# TSOC_PSoC4L.net
KiCad netlist of a schematic drawn in EAGLE
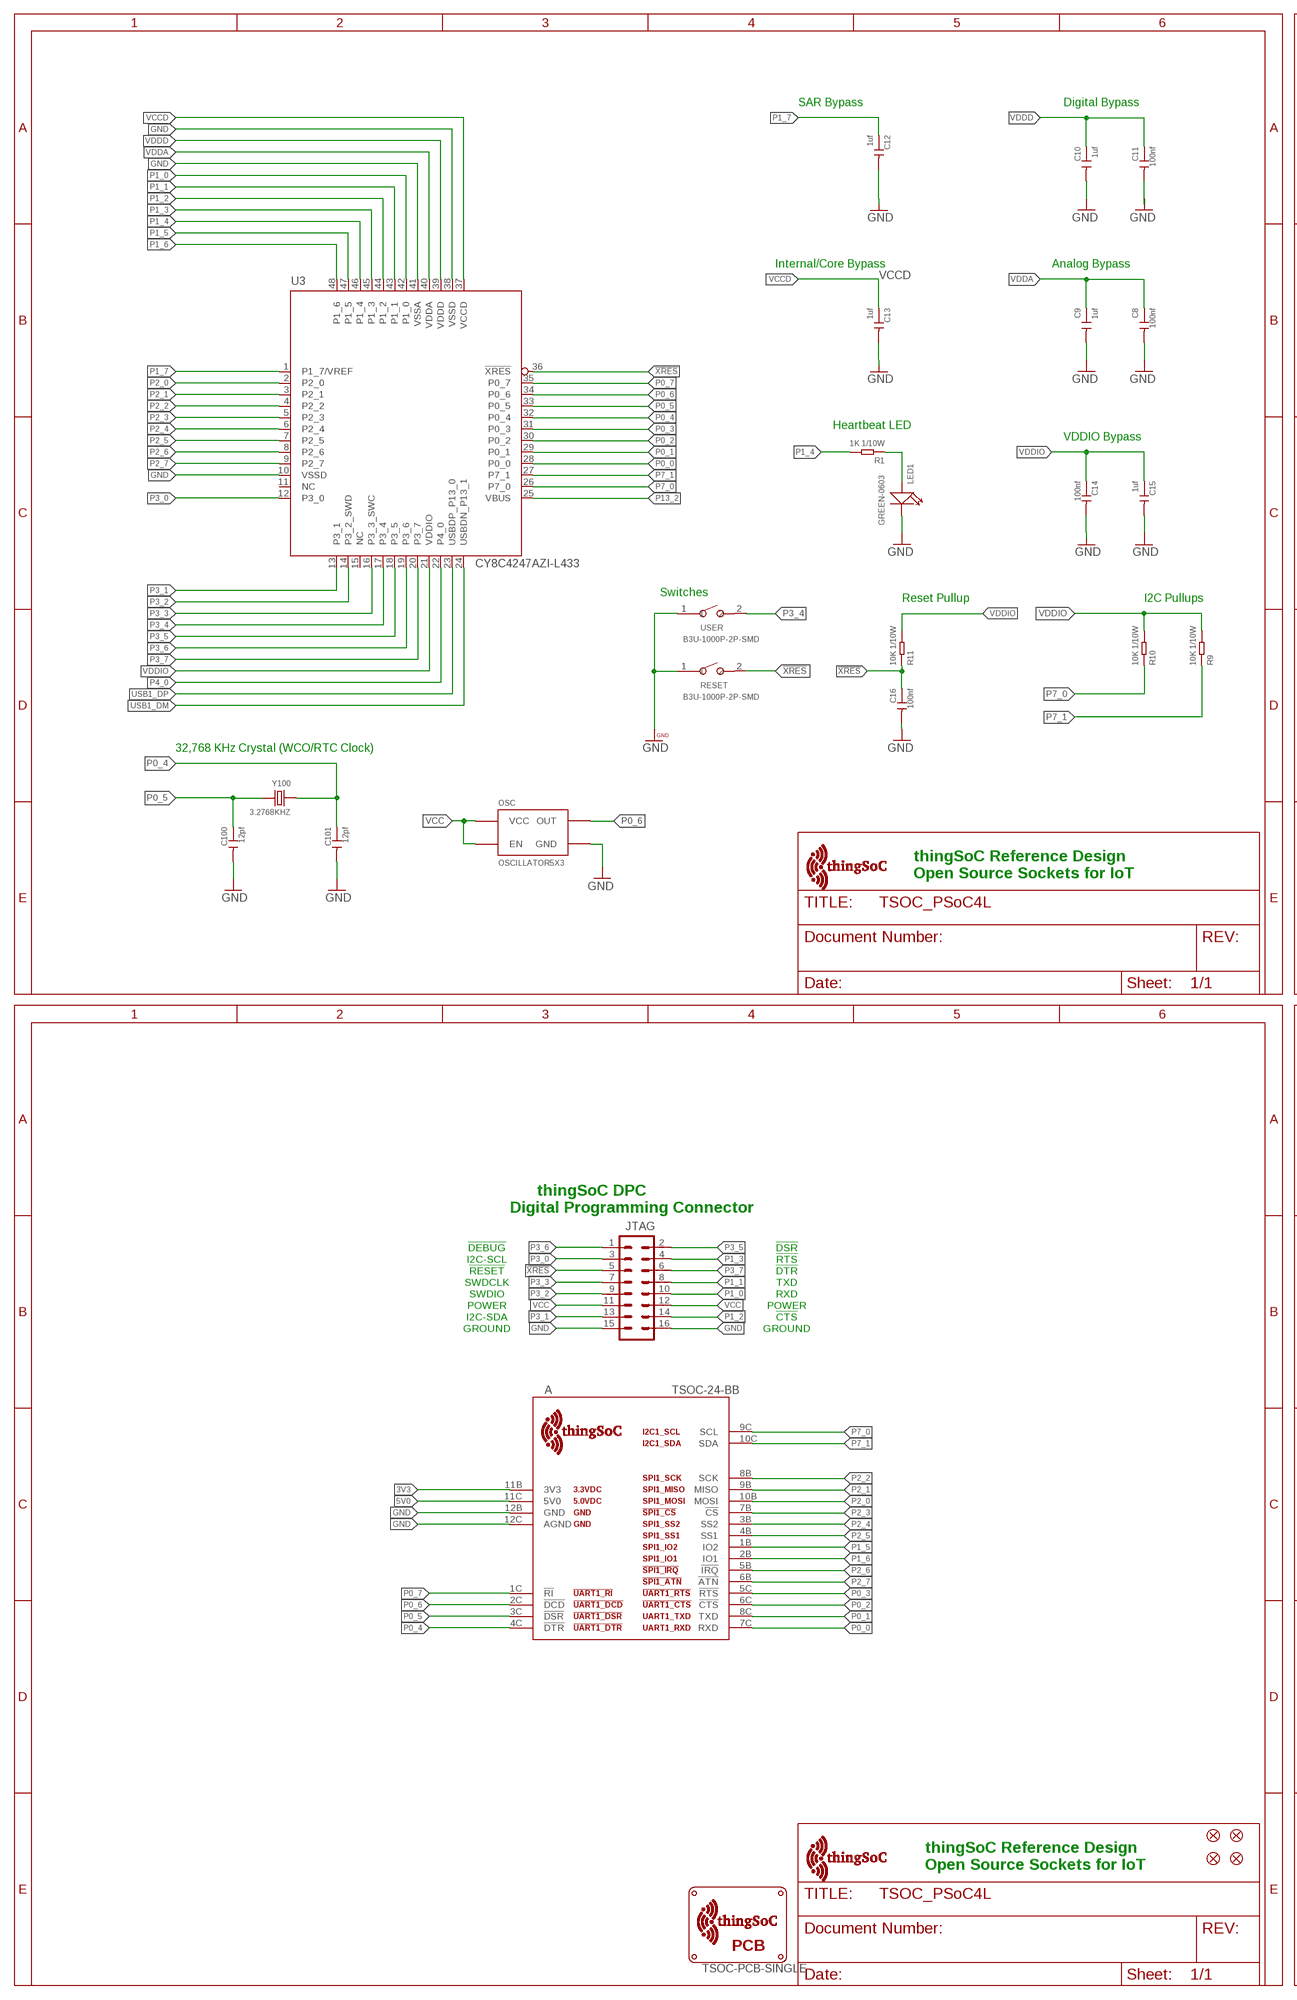
[diagram p0: schematic, sheet 1, part 1 of 2]
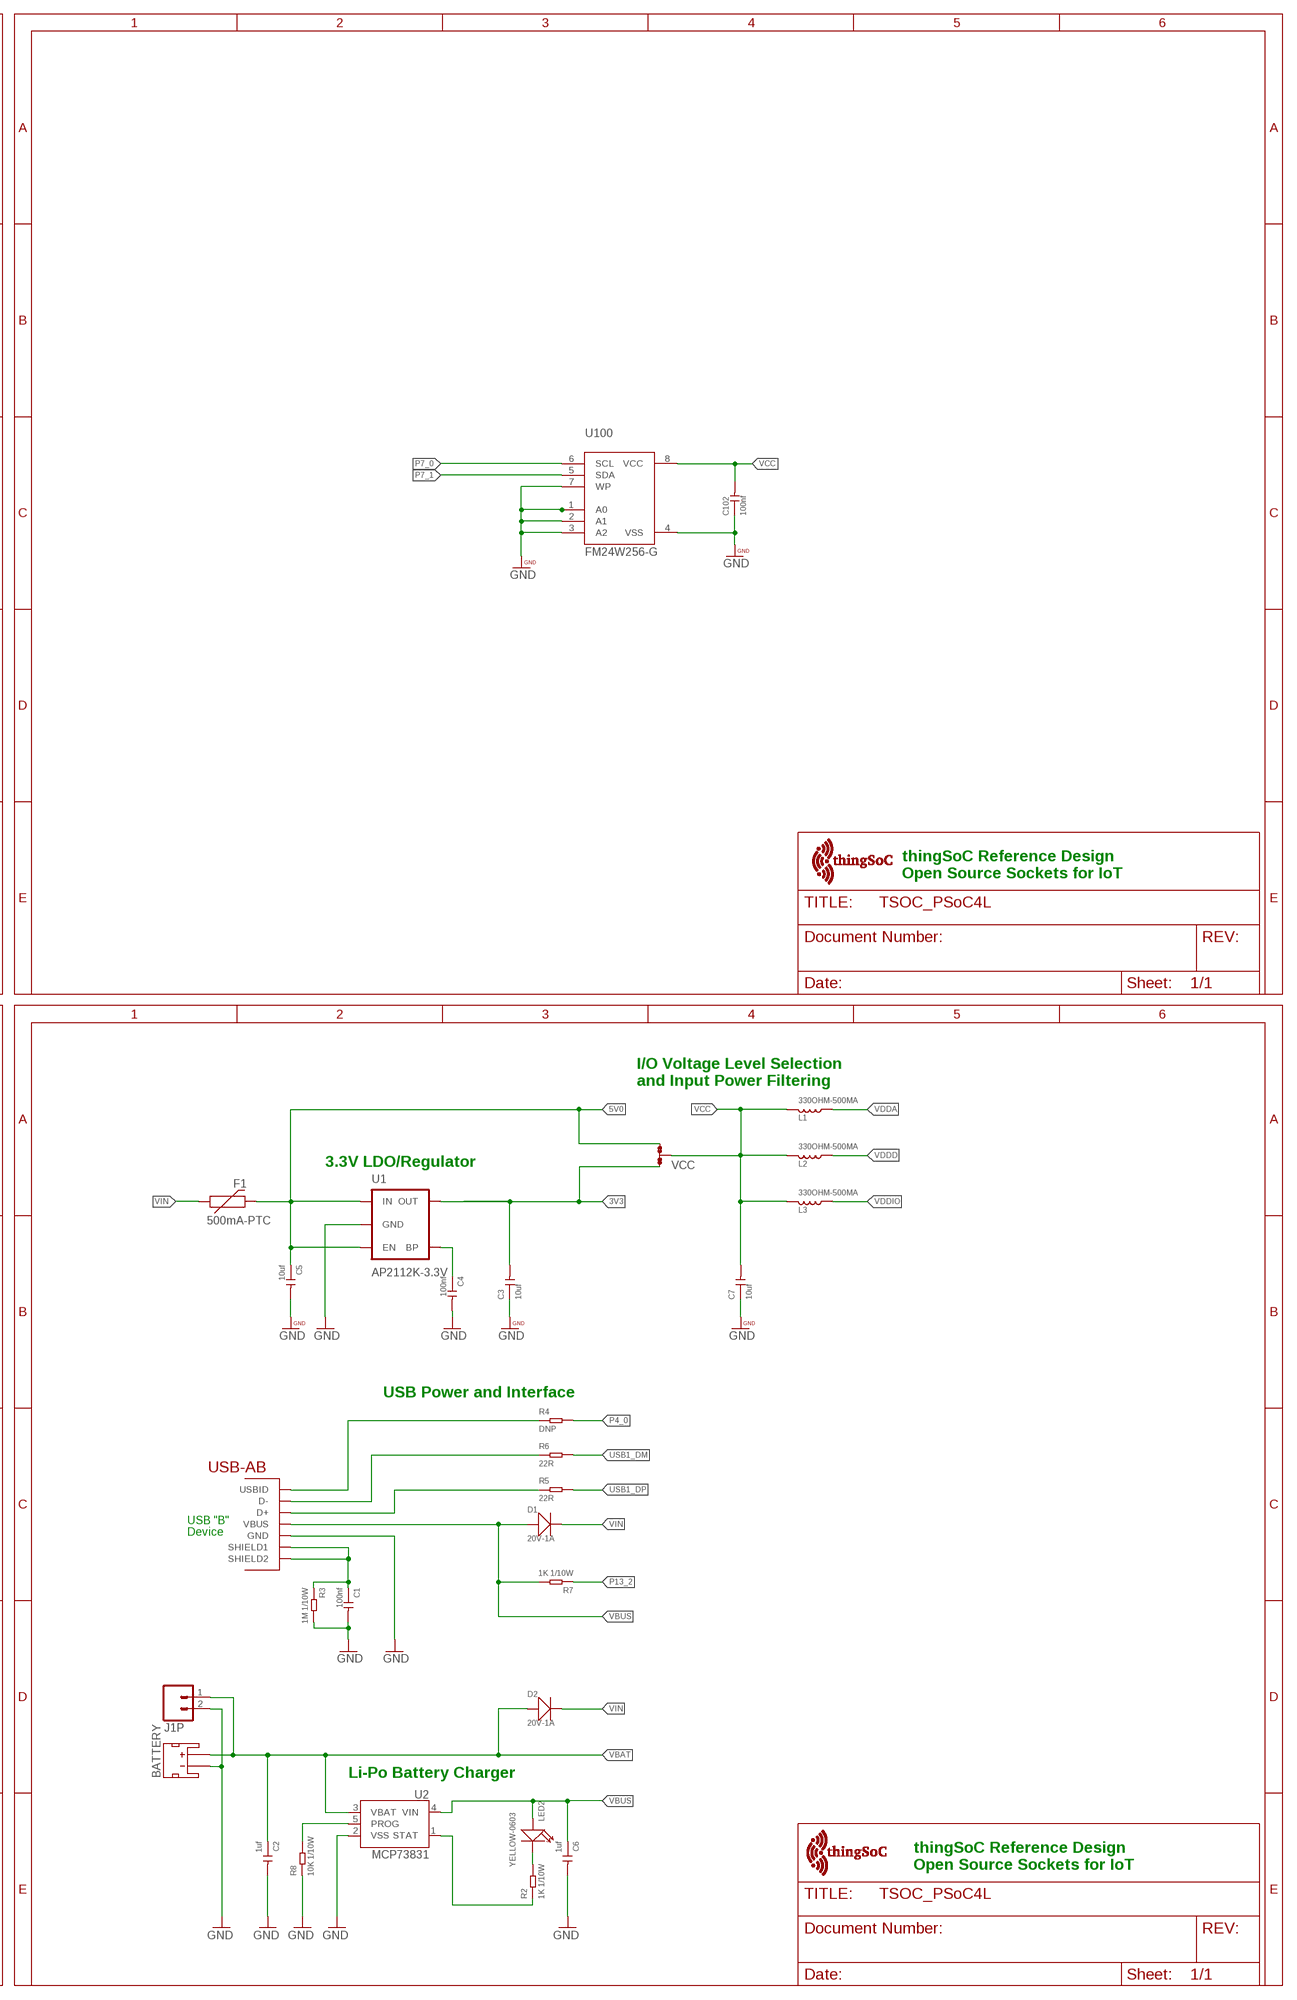
[diagram p1: schematic, sheet 1, part 2 of 2]

(export (version "E")
  (design (tool "Eeschema 10.0.6"))
  (components
    (comp (ref "$$U$1")
      (value "TSOC-LOGO-SMALL")
      (footprint "eagle-import:TSOC-LOGO-SML")
      (libsource (lib "eagle-import") (part "TSOC-LOGO-SMALL"))
    )
    (comp (ref "$$U$2")
      (value "TSOC-LOGO-SMALL")
      (footprint "eagle-import:TSOC-LOGO-SML")
      (libsource (lib "eagle-import") (part "TSOC-LOGO-SMALL"))
    )
    (comp (ref "A")
      (value "TSOC-24-BB")
      (footprint "eagle-import:TSOC-BB-S24")
      (libsource (lib "eagle-import") (part "TSOC-24-BB"))
    )
    (comp (ref "BATTERY")
      (value "JST_2MM_MALE")
      (footprint "eagle-import:JST-2-SMD")
      (libsource (lib "eagle-import") (part "JST_2MM_MALE"))
    )
    (comp (ref "C1")
      (value "100nf")
      (footprint "eagle-import:C0603")
      (fields (field (name "MPN") "CC0603KRX7R9BB104"))
      (libsource (lib "eagle-import") (part "CERAMIC-100NF-50V-10%-X7R(0603)"))
    )
    (comp (ref "C2")
      (value "1uf")
      (footprint "eagle-import:C0603")
      (fields (field (name "MPN") "CC0603KRX7R8BB105"))
      (libsource (lib "eagle-import") (part "CERAMIC-1UF-25V-10%-X7R(0603)"))
    )
    (comp (ref "C3")
      (value "10uf")
      (footprint "eagle-import:C0603")
      (fields (field (name "MPN") "CC0603KRX5R6BB106"))
      (libsource (lib "eagle-import") (part "CERAMIC-10UF-10V-10%-X5R(0603)"))
    )
    (comp (ref "C4")
      (value "100nf")
      (footprint "eagle-import:C0603")
      (fields (field (name "MPN") "CC0603KRX7R9BB104"))
      (libsource (lib "eagle-import") (part "CERAMIC-100NF-50V-10%-X7R(0603)"))
    )
    (comp (ref "C5")
      (value "10uf")
      (footprint "eagle-import:C0603")
      (fields (field (name "MPN") "CC0603KRX5R6BB106"))
      (libsource (lib "eagle-import") (part "CERAMIC-10UF-10V-10%-X5R(0603)"))
    )
    (comp (ref "C6")
      (value "1uf")
      (footprint "eagle-import:C0603")
      (fields (field (name "MPN") "CC0603KRX7R8BB105"))
      (libsource (lib "eagle-import") (part "CERAMIC-1UF-25V-10%-X7R(0603)"))
    )
    (comp (ref "C7")
      (value "10uf")
      (footprint "eagle-import:C0603")
      (fields (field (name "MPN") "CC0603KRX5R6BB106"))
      (libsource (lib "eagle-import") (part "CERAMIC-10UF-10V-10%-X5R(0603)"))
    )
    (comp (ref "C8")
      (value "100nf")
      (footprint "eagle-import:C0603")
      (fields (field (name "MPN") "CC0603KRX7R9BB104"))
      (libsource (lib "eagle-import") (part "CERAMIC-100NF-50V-10%-X7R(0603)"))
    )
    (comp (ref "C9")
      (value "1uf")
      (footprint "eagle-import:C0603")
      (fields (field (name "MPN") "CC0603KRX7R8BB105"))
      (libsource (lib "eagle-import") (part "CERAMIC-1UF-25V-10%-X7R(0603)"))
    )
    (comp (ref "C10")
      (value "1uf")
      (footprint "eagle-import:C0603")
      (fields (field (name "MPN") "CC0603KRX7R8BB105"))
      (libsource (lib "eagle-import") (part "CERAMIC-1UF-25V-10%-X7R(0603)"))
    )
    (comp (ref "C11")
      (value "100nf")
      (footprint "eagle-import:C0603")
      (fields (field (name "MPN") "CC0603KRX7R9BB104"))
      (libsource (lib "eagle-import") (part "CERAMIC-100NF-50V-10%-X7R(0603)"))
    )
    (comp (ref "C12")
      (value "1uf")
      (footprint "eagle-import:C0603")
      (fields (field (name "MPN") "CC0603KRX7R8BB105"))
      (libsource (lib "eagle-import") (part "CERAMIC-1UF-25V-10%-X7R(0603)"))
    )
    (comp (ref "C13")
      (value "1uf")
      (footprint "eagle-import:C0603")
      (fields (field (name "MPN") "CC0603KRX7R8BB105"))
      (libsource (lib "eagle-import") (part "CERAMIC-1UF-25V-10%-X7R(0603)"))
    )
    (comp (ref "C14")
      (value "100nf")
      (footprint "eagle-import:C0603")
      (fields (field (name "MPN") "CC0603KRX7R9BB104"))
      (libsource (lib "eagle-import") (part "CERAMIC-100NF-50V-10%-X7R(0603)"))
    )
    (comp (ref "C15")
      (value "1uf")
      (footprint "eagle-import:C0603")
      (fields (field (name "MPN") "CC0603KRX7R8BB105"))
      (libsource (lib "eagle-import") (part "CERAMIC-1UF-25V-10%-X7R(0603)"))
    )
    (comp (ref "C16")
      (value "100nf")
      (footprint "eagle-import:C0603")
      (fields (field (name "MPN") "CC0603KRX7R9BB104"))
      (libsource (lib "eagle-import") (part "CERAMIC-100NF-50V-10%-X7R(0603)"))
    )
    (comp (ref "C100")
      (value "12pf")
      (footprint "eagle-import:C0603")
      (fields (field (name "MPN") "CC0603JRNPO9BN120"))
      (libsource (lib "eagle-import") (part "CERAMIC-12PF-50V-5%-NPO(0603)"))
    )
    (comp (ref "C101")
      (value "12pf")
      (footprint "eagle-import:C0603")
      (fields (field (name "MPN") "CC0603JRNPO9BN120"))
      (libsource (lib "eagle-import") (part "CERAMIC-12PF-50V-5%-NPO(0603)"))
    )
    (comp (ref "C102")
      (value "100nf")
      (footprint "eagle-import:C0603")
      (fields (field (name "MPN") "CC0603KRX7R9BB104"))
      (libsource (lib "eagle-import") (part "CERAMIC-100NF-50V-10%-X7R(0603)"))
    )
    (comp (ref "D1")
      (value "20V-1A")
      (footprint "eagle-import:SOD-123")
      (fields (field (name "MPN") "B5819W"))
      (libsource (lib "eagle-import") (part "SMD-DIODE-SCHOTTKY-20V-1A(SOD-123)"))
    )
    (comp (ref "D2")
      (value "20V-1A")
      (footprint "eagle-import:SOD-123")
      (fields (field (name "MPN") "B5819W"))
      (libsource (lib "eagle-import") (part "SMD-DIODE-SCHOTTKY-20V-1A(SOD-123)"))
    )
    (comp (ref "F1")
      (value "500mA-PTC")
      (footprint "eagle-import:PTC-1206")
      (libsource (lib "eagle-import") (part "PTCSMD"))
    )
    (comp (ref "FID1")
      (value "FIDUCIALUFIDUCIAL")
      (footprint "eagle-import:MICRO-FIDUCIAL")
      (libsource (lib "eagle-import") (part "FIDUCIALUFIDUCIAL"))
    )
    (comp (ref "FID2")
      (value "FIDUCIALUFIDUCIAL")
      (footprint "eagle-import:MICRO-FIDUCIAL")
      (libsource (lib "eagle-import") (part "FIDUCIALUFIDUCIAL"))
    )
    (comp (ref "FID3")
      (value "FIDUCIALUFIDUCIAL")
      (footprint "eagle-import:MICRO-FIDUCIAL")
      (libsource (lib "eagle-import") (part "FIDUCIALUFIDUCIAL"))
    )
    (comp (ref "FID4")
      (value "FIDUCIALUFIDUCIAL")
      (footprint "eagle-import:MICRO-FIDUCIAL")
      (libsource (lib "eagle-import") (part "FIDUCIALUFIDUCIAL"))
    )
    (comp (ref "J1P")
      (value "M02-JST-2-PTH-NO_SILK")
      (footprint "eagle-import:JST-2-PTH-NS")
      (libsource (lib "eagle-import") (part "M02-JST-2-PTH-NO_SILK"))
    )
    (comp (ref "JTAG")
      (value "M08X2")
      (footprint "eagle-import:2X8")
      (libsource (lib "eagle-import") (part "M08X2"))
    )
    (comp (ref "L1")
      (value "330OHM-500MA")
      (footprint "eagle-import:L0603")
      (fields (field (name "MPN") "BLM18AG121SN1D"))
      (libsource (lib "eagle-import") (part "SMD-FERRITE-CHIP-120-OHM-500MA(0603)"))
    )
    (comp (ref "L2")
      (value "330OHM-500MA")
      (footprint "eagle-import:L0603")
      (fields (field (name "MPN") "BLM18AG121SN1D"))
      (libsource (lib "eagle-import") (part "SMD-FERRITE-CHIP-120-OHM-500MA(0603)"))
    )
    (comp (ref "L3")
      (value "330OHM-500MA")
      (footprint "eagle-import:L0603")
      (fields (field (name "MPN") "BLM18AG121SN1D"))
      (libsource (lib "eagle-import") (part "SMD-FERRITE-CHIP-120-OHM-500MA(0603)"))
    )
    (comp (ref "LED1")
      (value "GREEN-0603")
      (footprint "eagle-import:LED-0603")
      (fields (field (name "MPN") "19-217-G7C-AN1P2-3T"))
      (libsource (lib "eagle-import") (part "SMD-LED-CLEAR-GREEN(0603)"))
    )
    (comp (ref "LED2")
      (value "YELLOW-0603")
      (footprint "eagle-import:LED-0603")
      (fields (field (name "MPN") "19-217-Y5C-AM1N1VY-3T"))
      (libsource (lib "eagle-import") (part "SMD-LED-CLEAR-YELLOW(0603)"))
    )
    (comp (ref "OSC")
      (value "OSCILLATOR5X3")
      (footprint "eagle-import:CRYSTAL-SMD-5X3")
      (libsource (lib "eagle-import") (part "OSCILLATOR5X3"))
    )
    (comp (ref "R1")
      (value "1K 1/10W")
      (footprint "eagle-import:R0603")
      (fields (field (name "MPN") "RC0603JR-071KL"))
      (libsource (lib "eagle-import") (part "SMD-RES-1K-5%-1/10W(0603)"))
    )
    (comp (ref "R2")
      (value "1K 1/10W")
      (footprint "eagle-import:R0603")
      (fields (field (name "MPN") "RC0603JR-071KL"))
      (libsource (lib "eagle-import") (part "SMD-RES-1K-5%-1/10W(0603)"))
    )
    (comp (ref "R3")
      (value "1M 1/10W")
      (footprint "eagle-import:R0603")
      (fields (field (name "MPN") "RC0603JR-071ML"))
      (libsource (lib "eagle-import") (part "SMD-RES-1M-5%-1/10W(0603)"))
    )
    (comp (ref "R4")
      (value "DNP")
      (footprint "eagle-import:R0603")
      (fields (field (name "MPN") "RC0603JR-0722RL"))
      (libsource (lib "eagle-import") (part "SMD-RES-22R-5%-1/10W(0603)"))
    )
    (comp (ref "R5")
      (value "22R")
      (footprint "eagle-import:R0603")
      (fields (field (name "MPN") "RC0603JR-0722RL"))
      (libsource (lib "eagle-import") (part "SMD-RES-22R-5%-1/10W(0603)"))
    )
    (comp (ref "R6")
      (value "22R")
      (footprint "eagle-import:R0603")
      (fields (field (name "MPN") "RC0603JR-0722RL"))
      (libsource (lib "eagle-import") (part "SMD-RES-22R-5%-1/10W(0603)"))
    )
    (comp (ref "R7")
      (value "1K 1/10W")
      (footprint "eagle-import:R0603")
      (fields (field (name "MPN") "RC0603JR-071KL"))
      (libsource (lib "eagle-import") (part "SMD-RES-1K-5%-1/10W(0603)"))
    )
    (comp (ref "R8")
      (value "10K 1/10W")
      (footprint "eagle-import:R0603")
      (fields (field (name "MPN") "RC0603JR-0710KL"))
      (libsource (lib "eagle-import") (part "SMD-RES-10K-5%-1/10W(0603)"))
    )
    (comp (ref "R9")
      (value "10K 1/10W")
      (footprint "eagle-import:R0603")
      (fields (field (name "MPN") "RC0603JR-0710KL"))
      (libsource (lib "eagle-import") (part "SMD-RES-10K-5%-1/10W(0603)"))
    )
    (comp (ref "R10")
      (value "10K 1/10W")
      (footprint "eagle-import:R0603")
      (fields (field (name "MPN") "RC0603JR-0710KL"))
      (libsource (lib "eagle-import") (part "SMD-RES-10K-5%-1/10W(0603)"))
    )
    (comp (ref "R11")
      (value "10K 1/10W")
      (footprint "eagle-import:R0603")
      (fields (field (name "MPN") "RC0603JR-0710KL"))
      (libsource (lib "eagle-import") (part "SMD-RES-10K-5%-1/10W(0603)"))
    )
    (comp (ref "RESET")
      (value "B3U-1000P-2P-SMD")
      (footprint "eagle-import:SW2-2.6-3.0X2.5X1.2+0.4MM")
      (libsource (lib "eagle-import") (part "SMD-BUTTON(2P-3.0X2.5X1.2+0.4MM)-B3U-1000P-2P-SMD"))
    )
    (comp (ref "U$1")
      (value "TSOC-PCB-SINGLE")
      (footprint "eagle-import:TSOC-BB-BRD-DIM")
      (libsource (lib "eagle-import") (part "TSOC-PCB-SINGLE"))
    )
    (comp (ref "U$100")
      (value "TSOC-LOGO-LRG")
      (footprint "eagle-import:TSOC-LOGO-LRG")
      (libsource (lib "eagle-import") (part "TSOC-LOGO-LRG"))
    )
    (comp (ref "U$101")
      (value "TSOC-LOGO-SMALL")
      (footprint "eagle-import:TSOC-LOGO-SML")
      (libsource (lib "eagle-import") (part "TSOC-LOGO-SMALL"))
    )
    (comp (ref "U1")
      (value "AP2112K-3.3V")
      (footprint "eagle-import:SOT23-5")
      (libsource (lib "eagle-import") (part "V_REG_LDOSMD"))
    )
    (comp (ref "U2")
      (value "MCP73831")
      (footprint "eagle-import:SOT23-5")
      (libsource (lib "eagle-import") (part "MCP73831"))
    )
    (comp (ref "U3")
      (value "CY8C4247AZI-L433")
      (footprint "eagle-import:TQFP-7X7-48")
      (libsource (lib "eagle-import") (part "CY8C4247AZI-L433"))
    )
    (comp (ref "U100")
      (value "FM24W256-G")
      (footprint "eagle-import:SO08")
      (libsource (lib "eagle-import") (part "FM24W256-G"))
    )
    (comp (ref "USB")
      (value "USB_AB")
      (footprint "eagle-import:USB-AB-MICRO-SMD")
      (libsource (lib "eagle-import") (part "USB_AB"))
    )
    (comp (ref "USER")
      (value "B3U-1000P-2P-SMD")
      (footprint "eagle-import:SW2-2.6-3.0X2.5X1.2+0.4MM")
      (libsource (lib "eagle-import") (part "SMD-BUTTON(2P-3.0X2.5X1.2+0.4MM)-B3U-1000P-2P-SMD"))
    )
    (comp (ref "VCC")
      (value "JMP-3-1_2")
      (footprint "eagle-import:JMP-3-1_2")
      (libsource (lib "eagle-import") (part "JMP-3-1_2"))
    )
    (comp (ref "Y100")
      (value "3.2768KHZ")
      (footprint "eagle-import:X2-SMD-L2.0X1.2X0.55MM")
      (fields (field (name "MPN") "FC-12M"))
      (libsource (lib "eagle-import") (part "SMD-CRYSTAL-32.768KHZ-12.5PF-20PPM-90K(2P-L2.0X1.2MM)"))
    )
  )
  (nets
    (net (code "1") (name "/~{XRES}") (class "Default")
      (node (ref "C16") (pin "1") (pinfunction "1_1") (pintype "passive"))
      (node (ref "JTAG") (pin "5") (pinfunction "5_5") (pintype "passive"))
      (node (ref "R11") (pin "1") (pinfunction "1_1") (pintype "passive"))
      (node (ref "RESET") (pin "2") (pinfunction "2_2") (pintype "bidirectional"))
      (node (ref "U3") (pin "36") (pinfunction "~{XRES}_36") (pintype "bidirectional"))
    )
    (net (code "2") (name "3V3") (class "Default")
      (node (ref "A") (pin "11B") (pinfunction "3V3_11B") (pintype "bidirectional"))
      (node (ref "C3") (pin "2") (pinfunction "2_2") (pintype "passive"))
      (node (ref "U1") (pin "5") (pinfunction "OUT_5") (pintype "passive"))
      (node (ref "VCC") (pin "1") (pinfunction "1_1") (pintype "passive"))
    )
    (net (code "3") (name "5V0") (class "Default")
      (node (ref "A") (pin "11C") (pinfunction "5V0_11C") (pintype "bidirectional"))
      (node (ref "C5") (pin "1") (pinfunction "1_1") (pintype "passive"))
      (node (ref "F1") (pin "2") (pinfunction "2_2") (pintype "bidirectional"))
      (node (ref "U1") (pin "1") (pinfunction "IN_1") (pintype "input"))
      (node (ref "U1") (pin "3") (pinfunction "EN_3") (pintype "input"))
      (node (ref "VCC") (pin "3") (pinfunction "3_3") (pintype "passive"))
    )
    (net (code "4") (name "GND") (class "Default")
      (node (ref "A") (pin "12B") (pinfunction "GND_12B") (pintype "bidirectional"))
      (node (ref "A") (pin "12C") (pinfunction "AGND_12C") (pintype "bidirectional"))
      (node (ref "BATTERY") (pin "1") (pinfunction "-_1") (pintype "bidirectional"))
      (node (ref "C1") (pin "2") (pinfunction "2_2") (pintype "passive"))
      (node (ref "C10") (pin "2") (pinfunction "2_2") (pintype "passive"))
      (node (ref "C100") (pin "2") (pinfunction "2_2") (pintype "passive"))
      (node (ref "C101") (pin "2") (pinfunction "2_2") (pintype "passive"))
      (node (ref "C102") (pin "1") (pinfunction "1_1") (pintype "passive"))
      (node (ref "C11") (pin "2") (pinfunction "2_2") (pintype "passive"))
      (node (ref "C12") (pin "2") (pinfunction "2_2") (pintype "passive"))
      (node (ref "C13") (pin "2") (pinfunction "2_2") (pintype "passive"))
      (node (ref "C14") (pin "2") (pinfunction "2_2") (pintype "passive"))
      (node (ref "C15") (pin "2") (pinfunction "2_2") (pintype "passive"))
      (node (ref "C16") (pin "2") (pinfunction "2_2") (pintype "passive"))
      (node (ref "C2") (pin "2") (pinfunction "2_2") (pintype "passive"))
      (node (ref "C3") (pin "1") (pinfunction "1_1") (pintype "passive"))
      (node (ref "C4") (pin "2") (pinfunction "2_2") (pintype "passive"))
      (node (ref "C5") (pin "2") (pinfunction "2_2") (pintype "passive"))
      (node (ref "C6") (pin "2") (pinfunction "2_2") (pintype "passive"))
      (node (ref "C7") (pin "1") (pinfunction "1_1") (pintype "passive"))
      (node (ref "C8") (pin "2") (pinfunction "2_2") (pintype "passive"))
      (node (ref "C9") (pin "2") (pinfunction "2_2") (pintype "passive"))
      (node (ref "J1P") (pin "2") (pinfunction "2_2") (pintype "passive"))
      (node (ref "JTAG") (pin "15") (pinfunction "15_15") (pintype "passive"))
      (node (ref "JTAG") (pin "16") (pinfunction "16_16") (pintype "passive"))
      (node (ref "LED1") (pin "-") (pinfunction "-_-") (pintype "passive"))
      (node (ref "OSC") (pin "2") (pinfunction "GND_2") (pintype "bidirectional"))
      (node (ref "R3") (pin "2") (pinfunction "2_2") (pintype "passive"))
      (node (ref "R8") (pin "1") (pinfunction "1_1") (pintype "passive"))
      (node (ref "RESET") (pin "1") (pinfunction "1_1") (pintype "bidirectional"))
      (node (ref "U1") (pin "2") (pinfunction "GND_2") (pintype "input"))
      (node (ref "U100") (pin "1") (pinfunction "A0_1") (pintype "bidirectional"))
      (node (ref "U100") (pin "2") (pinfunction "A1_2") (pintype "bidirectional"))
      (node (ref "U100") (pin "3") (pinfunction "A2_3") (pintype "bidirectional"))
      (node (ref "U100") (pin "4") (pinfunction "VSS_4") (pintype "power_in"))
      (node (ref "U100") (pin "7") (pinfunction "WP_7") (pintype "bidirectional"))
      (node (ref "U2") (pin "2") (pinfunction "VSS_2") (pintype "power_in"))
      (node (ref "U3") (pin "10") (pinfunction "VSSD_10") (pintype "bidirectional"))
      (node (ref "U3") (pin "38") (pinfunction "VSSD_38") (pintype "bidirectional"))
      (node (ref "U3") (pin "41") (pinfunction "VSSA_41") (pintype "bidirectional"))
      (node (ref "USB") (pin "GND") (pinfunction "GND_GND") (pintype "bidirectional"))
      (node (ref "USER") (pin "1") (pinfunction "1_1") (pintype "bidirectional"))
    )
    (net (code "5") (name "Net-(C1-Pad1)") (class "Default")
      (node (ref "C1") (pin "1") (pinfunction "1_1") (pintype "passive"))
      (node (ref "R3") (pin "1") (pinfunction "1_1") (pintype "passive"))
      (node (ref "USB") (pin "SHIELD1") (pinfunction "SHIELD1_SHIELD1") (pintype "bidirectional"))
      (node (ref "USB") (pin "SHIELD2") (pinfunction "SHIELD2_SHIELD2") (pintype "bidirectional"))
    )
    (net (code "6") (name "Net-(LED1-Pad+)") (class "Default")
      (node (ref "LED1") (pin "+") (pinfunction "+_+") (pintype "passive"))
      (node (ref "R1") (pin "1") (pinfunction "1_1") (pintype "passive"))
    )
    (net (code "7") (name "Net-(LED2-Pad-)") (class "Default")
      (node (ref "LED2") (pin "-") (pinfunction "-_-") (pintype "passive"))
      (node (ref "R2") (pin "2") (pinfunction "2_2") (pintype "passive"))
    )
    (net (code "8") (name "Net-(R5-Pad1)") (class "Default")
      (node (ref "R5") (pin "1") (pinfunction "1_1") (pintype "passive"))
      (node (ref "USB") (pin "D+") (pinfunction "D+_D+") (pintype "bidirectional"))
    )
    (net (code "9") (name "Net-(R6-Pad1)") (class "Default")
      (node (ref "R6") (pin "1") (pinfunction "1_1") (pintype "passive"))
      (node (ref "USB") (pin "D-") (pinfunction "D-_D-") (pintype "bidirectional"))
    )
    (net (code "10") (name "Net-(U1-BP)") (class "Default")
      (node (ref "C4") (pin "1") (pinfunction "1_1") (pintype "passive"))
      (node (ref "U1") (pin "4") (pinfunction "BP_4") (pintype "input"))
    )
    (net (code "11") (name "Net-(U2-PROG)") (class "Default")
      (node (ref "R8") (pin "2") (pinfunction "2_2") (pintype "passive"))
      (node (ref "U2") (pin "5") (pinfunction "PROG_5") (pintype "input"))
    )
    (net (code "12") (name "Net-(U2-STAT)") (class "Default")
      (node (ref "R2") (pin "1") (pinfunction "1_1") (pintype "passive"))
      (node (ref "U2") (pin "1") (pinfunction "STAT_1") (pintype "output"))
    )
    (net (code "13") (name "Net-(USB-USBID)") (class "Default")
      (node (ref "R4") (pin "1") (pinfunction "1_1") (pintype "passive"))
      (node (ref "USB") (pin "ID") (pinfunction "USBID_ID") (pintype "bidirectional"))
    )
    (net (code "14") (name "P0_0") (class "Default")
      (node (ref "A") (pin "7C") (pinfunction "RXD_7C") (pintype "bidirectional"))
      (node (ref "U3") (pin "28") (pinfunction "P0_0_28") (pintype "bidirectional"))
    )
    (net (code "15") (name "P0_1") (class "Default")
      (node (ref "A") (pin "8C") (pinfunction "TXD_8C") (pintype "bidirectional"))
      (node (ref "U3") (pin "29") (pinfunction "P0_1_29") (pintype "bidirectional"))
    )
    (net (code "16") (name "P0_2") (class "Default")
      (node (ref "A") (pin "6C") (pinfunction "~{CTS}_6C") (pintype "bidirectional"))
      (node (ref "U3") (pin "30") (pinfunction "P0_2_30") (pintype "input"))
    )
    (net (code "17") (name "P0_3") (class "Default")
      (node (ref "A") (pin "5C") (pinfunction "~{RTS}_5C") (pintype "bidirectional"))
      (node (ref "U3") (pin "31") (pinfunction "P0_3_31") (pintype "bidirectional"))
    )
    (net (code "18") (name "P0_4") (class "Default")
      (node (ref "A") (pin "4C") (pinfunction "~{DTR}_4C") (pintype "bidirectional"))
      (node (ref "C101") (pin "1") (pinfunction "1_1") (pintype "passive"))
      (node (ref "U3") (pin "32") (pinfunction "P0_4_32") (pintype "bidirectional"))
      (node (ref "Y100") (pin "1") (pinfunction "1_1") (pintype "passive"))
    )
    (net (code "19") (name "P0_5") (class "Default")
      (node (ref "A") (pin "3C") (pinfunction "~{DSR}_3C") (pintype "bidirectional"))
      (node (ref "C100") (pin "1") (pinfunction "1_1") (pintype "passive"))
      (node (ref "U3") (pin "33") (pinfunction "P0_5_33") (pintype "bidirectional"))
      (node (ref "Y100") (pin "2") (pinfunction "2_2") (pintype "passive"))
    )
    (net (code "20") (name "P0_6") (class "Default")
      (node (ref "A") (pin "2C") (pinfunction "~{DCD}_2C") (pintype "bidirectional"))
      (node (ref "OSC") (pin "3") (pinfunction "OUT_3") (pintype "bidirectional"))
      (node (ref "U3") (pin "34") (pinfunction "P0_6_34") (pintype "power_in"))
    )
    (net (code "21") (name "P0_7") (class "Default")
      (node (ref "A") (pin "1C") (pinfunction "~{RI}_1C") (pintype "bidirectional"))
      (node (ref "U3") (pin "35") (pinfunction "P0_7_35") (pintype "bidirectional"))
    )
    (net (code "22") (name "P1_0") (class "Default")
      (node (ref "JTAG") (pin "10") (pinfunction "10_10") (pintype "passive"))
      (node (ref "U3") (pin "42") (pinfunction "P1_0_42") (pintype "bidirectional"))
    )
    (net (code "23") (name "P1_1") (class "Default")
      (node (ref "JTAG") (pin "8") (pinfunction "8_8") (pintype "passive"))
      (node (ref "U3") (pin "43") (pinfunction "P1_1_43") (pintype "bidirectional"))
    )
    (net (code "24") (name "P1_2") (class "Default")
      (node (ref "JTAG") (pin "14") (pinfunction "14_14") (pintype "passive"))
      (node (ref "U3") (pin "44") (pinfunction "P1_2_44") (pintype "power_in"))
    )
    (net (code "25") (name "P1_3") (class "Default")
      (node (ref "JTAG") (pin "4") (pinfunction "4_4") (pintype "passive"))
      (node (ref "U3") (pin "45") (pinfunction "P1_3_45") (pintype "bidirectional"))
    )
    (net (code "26") (name "P1_4") (class "Default")
      (node (ref "R1") (pin "2") (pinfunction "2_2") (pintype "passive"))
      (node (ref "U3") (pin "46") (pinfunction "P1_4_46") (pintype "bidirectional"))
    )
    (net (code "27") (name "P1_5") (class "Default")
      (node (ref "A") (pin "1B") (pinfunction "IO2_1B") (pintype "bidirectional"))
      (node (ref "U3") (pin "47") (pinfunction "P1_5_47") (pintype "bidirectional"))
    )
    (net (code "28") (name "P1_6") (class "Default")
      (node (ref "A") (pin "2B") (pinfunction "IO1_2B") (pintype "bidirectional"))
      (node (ref "U3") (pin "48") (pinfunction "P1_6_48") (pintype "bidirectional"))
    )
    (net (code "29") (name "P1_7") (class "Default")
      (node (ref "C12") (pin "1") (pinfunction "1_1") (pintype "passive"))
      (node (ref "U3") (pin "1") (pinfunction "P1_7/VREF_1") (pintype "bidirectional"))
    )
    (net (code "30") (name "P2_0") (class "Default")
      (node (ref "A") (pin "10B") (pinfunction "MOSI_10B") (pintype "bidirectional"))
      (node (ref "U3") (pin "2") (pinfunction "P2_0_2") (pintype "bidirectional"))
    )
    (net (code "31") (name "P2_1") (class "Default")
      (node (ref "A") (pin "9B") (pinfunction "MISO_9B") (pintype "bidirectional"))
      (node (ref "U3") (pin "3") (pinfunction "P2_1_3") (pintype "bidirectional"))
    )
    (net (code "32") (name "P2_2") (class "Default")
      (node (ref "A") (pin "8B") (pinfunction "SCK_8B") (pintype "bidirectional"))
      (node (ref "U3") (pin "4") (pinfunction "P2_2_4") (pintype "power_in"))
    )
    (net (code "33") (name "P2_3") (class "Default")
      (node (ref "A") (pin "7B") (pinfunction "~{CS}_7B") (pintype "bidirectional"))
      (node (ref "U3") (pin "5") (pinfunction "P2_3_5") (pintype "bidirectional"))
    )
    (net (code "34") (name "P2_4") (class "Default")
      (node (ref "A") (pin "3B") (pinfunction "SS2_3B") (pintype "bidirectional"))
      (node (ref "U3") (pin "6") (pinfunction "P2_4_6") (pintype "bidirectional"))
    )
    (net (code "35") (name "P2_5") (class "Default")
      (node (ref "A") (pin "4B") (pinfunction "SS1_4B") (pintype "bidirectional"))
      (node (ref "U3") (pin "7") (pinfunction "P2_5_7") (pintype "bidirectional"))
    )
    (net (code "36") (name "P2_6") (class "Default")
      (node (ref "A") (pin "5B") (pinfunction "~{IRQ}_5B") (pintype "bidirectional"))
      (node (ref "U3") (pin "8") (pinfunction "P2_6_8") (pintype "power_in"))
    )
    (net (code "37") (name "P2_7") (class "Default")
      (node (ref "A") (pin "6B") (pinfunction "~{ATN}_6B") (pintype "bidirectional"))
      (node (ref "U3") (pin "9") (pinfunction "P2_7_9") (pintype "bidirectional"))
    )
    (net (code "38") (name "P3_0") (class "Default")
      (node (ref "JTAG") (pin "3") (pinfunction "3_3") (pintype "passive"))
      (node (ref "U3") (pin "12") (pinfunction "P3_0_12") (pintype "bidirectional"))
    )
    (net (code "39") (name "P3_1") (class "Default")
      (node (ref "JTAG") (pin "13") (pinfunction "13_13") (pintype "passive"))
      (node (ref "U3") (pin "13") (pinfunction "P3_1_13") (pintype "bidirectional"))
    )
    (net (code "40") (name "P3_2") (class "Default")
      (node (ref "JTAG") (pin "9") (pinfunction "9_9") (pintype "passive"))
      (node (ref "U3") (pin "14") (pinfunction "P3_2_SWD_14") (pintype "bidirectional"))
    )
    (net (code "41") (name "P3_3") (class "Default")
      (node (ref "JTAG") (pin "7") (pinfunction "7_7") (pintype "passive"))
      (node (ref "U3") (pin "16") (pinfunction "P3_3_SWC_16") (pintype "bidirectional"))
    )
    (net (code "42") (name "P3_4") (class "Default")
      (node (ref "U3") (pin "17") (pinfunction "P3_4_17") (pintype "bidirectional"))
      (node (ref "USER") (pin "2") (pinfunction "2_2") (pintype "bidirectional"))
    )
    (net (code "43") (name "P3_5") (class "Default")
      (node (ref "JTAG") (pin "2") (pinfunction "2_2") (pintype "passive"))
      (node (ref "U3") (pin "18") (pinfunction "P3_5_18") (pintype "bidirectional"))
    )
    (net (code "44") (name "P3_6") (class "Default")
      (node (ref "JTAG") (pin "1") (pinfunction "1_1") (pintype "passive"))
      (node (ref "U3") (pin "19") (pinfunction "P3_6_19") (pintype "power_in"))
    )
    (net (code "45") (name "P3_7") (class "Default")
      (node (ref "JTAG") (pin "6") (pinfunction "6_6") (pintype "passive"))
      (node (ref "U3") (pin "20") (pinfunction "P3_7_20") (pintype "bidirectional"))
    )
    (net (code "46") (name "P4_0") (class "Default")
      (node (ref "R4") (pin "2") (pinfunction "2_2") (pintype "passive"))
      (node (ref "U3") (pin "22") (pinfunction "P4_0_22") (pintype "bidirectional"))
    )
    (net (code "47") (name "P7_0") (class "Default")
      (node (ref "A") (pin "9C") (pinfunction "SCL_9C") (pintype "bidirectional"))
      (node (ref "R10") (pin "1") (pinfunction "1_1") (pintype "passive"))
      (node (ref "U100") (pin "6") (pinfunction "SCL_6") (pintype "bidirectional"))
      (node (ref "U3") (pin "26") (pinfunction "P7_0_26") (pintype "bidirectional"))
    )
    (net (code "48") (name "P7_1") (class "Default")
      (node (ref "A") (pin "10C") (pinfunction "SDA_10C") (pintype "bidirectional"))
      (node (ref "R9") (pin "1") (pinfunction "1_1") (pintype "passive"))
      (node (ref "U100") (pin "5") (pinfunction "SDA_5") (pintype "bidirectional"))
      (node (ref "U3") (pin "27") (pinfunction "P7_1_27") (pintype "bidirectional"))
    )
    (net (code "49") (name "P13_2") (class "Default")
      (node (ref "R7") (pin "1") (pinfunction "1_1") (pintype "passive"))
      (node (ref "U3") (pin "25") (pinfunction "VBUS_25") (pintype "bidirectional"))
    )
    (net (code "50") (name "USB1_DM") (class "Default")
      (node (ref "R6") (pin "2") (pinfunction "2_2") (pintype "passive"))
      (node (ref "U3") (pin "24") (pinfunction "USBDN_P13_1_24") (pintype "bidirectional"))
    )
    (net (code "51") (name "USB1_DP") (class "Default")
      (node (ref "R5") (pin "2") (pinfunction "2_2") (pintype "passive"))
      (node (ref "U3") (pin "23") (pinfunction "USBDP_P13_0_23") (pintype "bidirectional"))
    )
    (net (code "52") (name "VBAT") (class "Default")
      (node (ref "BATTERY") (pin "2") (pinfunction "+_2") (pintype "bidirectional"))
      (node (ref "C2") (pin "1") (pinfunction "1_1") (pintype "passive"))
      (node (ref "D2") (pin "+") (pinfunction "+_+") (pintype "passive"))
      (node (ref "J1P") (pin "1") (pinfunction "1_1") (pintype "passive"))
      (node (ref "U2") (pin "3") (pinfunction "VBAT_3") (pintype "power_in"))
    )
    (net (code "53") (name "VBUS") (class "Default")
      (node (ref "C6") (pin "1") (pinfunction "1_1") (pintype "passive"))
      (node (ref "D1") (pin "+") (pinfunction "+_+") (pintype "passive"))
      (node (ref "LED2") (pin "+") (pinfunction "+_+") (pintype "passive"))
      (node (ref "R7") (pin "2") (pinfunction "2_2") (pintype "passive"))
      (node (ref "U2") (pin "4") (pinfunction "VIN_4") (pintype "power_in"))
      (node (ref "USB") (pin "VBUS") (pinfunction "VBUS_VBUS") (pintype "bidirectional"))
    )
    (net (code "54") (name "VCC") (class "Default")
      (node (ref "C102") (pin "2") (pinfunction "2_2") (pintype "passive"))
      (node (ref "C7") (pin "2") (pinfunction "2_2") (pintype "passive"))
      (node (ref "JTAG") (pin "11") (pinfunction "11_11") (pintype "passive"))
      (node (ref "JTAG") (pin "12") (pinfunction "12_12") (pintype "passive"))
      (node (ref "L1") (pin "1") (pinfunction "1_1") (pintype "passive"))
      (node (ref "L2") (pin "1") (pinfunction "1_1") (pintype "passive"))
      (node (ref "L3") (pin "1") (pinfunction "1_1") (pintype "passive"))
      (node (ref "OSC") (pin "1") (pinfunction "EN_1") (pintype "bidirectional"))
      (node (ref "OSC") (pin "4") (pinfunction "VCC_4") (pintype "bidirectional"))
      (node (ref "U100") (pin "8") (pinfunction "VCC_8") (pintype "power_in"))
      (node (ref "VCC") (pin "2") (pinfunction "2_2") (pintype "passive"))
    )
    (net (code "55") (name "VCCD") (class "Default")
      (node (ref "C13") (pin "1") (pinfunction "1_1") (pintype "passive"))
      (node (ref "U3") (pin "37") (pinfunction "VCCD_37") (pintype "bidirectional"))
    )
    (net (code "56") (name "VDDA") (class "Default")
      (node (ref "C8") (pin "1") (pinfunction "1_1") (pintype "passive"))
      (node (ref "C9") (pin "1") (pinfunction "1_1") (pintype "passive"))
      (node (ref "L1") (pin "2") (pinfunction "2_2") (pintype "passive"))
      (node (ref "U3") (pin "40") (pinfunction "VDDA_40") (pintype "bidirectional"))
    )
    (net (code "57") (name "VDDD") (class "Default")
      (node (ref "C10") (pin "1") (pinfunction "1_1") (pintype "passive"))
      (node (ref "C11") (pin "1") (pinfunction "1_1") (pintype "passive"))
      (node (ref "L2") (pin "2") (pinfunction "2_2") (pintype "passive"))
      (node (ref "U3") (pin "39") (pinfunction "VDDD_39") (pintype "bidirectional"))
    )
    (net (code "58") (name "VDDIO") (class "Default")
      (node (ref "C14") (pin "1") (pinfunction "1_1") (pintype "passive"))
      (node (ref "C15") (pin "1") (pinfunction "1_1") (pintype "passive"))
      (node (ref "L3") (pin "2") (pinfunction "2_2") (pintype "passive"))
      (node (ref "R10") (pin "2") (pinfunction "2_2") (pintype "passive"))
      (node (ref "R11") (pin "2") (pinfunction "2_2") (pintype "passive"))
      (node (ref "R9") (pin "2") (pinfunction "2_2") (pintype "passive"))
      (node (ref "U3") (pin "21") (pinfunction "VDDIO_21") (pintype "bidirectional"))
    )
    (net (code "59") (name "VIN") (class "Default")
      (node (ref "D1") (pin "-") (pinfunction "-_-") (pintype "passive"))
      (node (ref "D2") (pin "-") (pinfunction "-_-") (pintype "passive"))
      (node (ref "F1") (pin "1") (pinfunction "1_1") (pintype "bidirectional"))
    )
    (net (code "60") (name "unconnected-(BATTERY-PAD1-PadNC1)") (class "Default")
      (node (ref "BATTERY") (pin "NC1") (pinfunction "PAD1_NC1") (pintype "bidirectional"))
    )
    (net (code "61") (name "unconnected-(BATTERY-PAD2-PadNC2)") (class "Default")
      (node (ref "BATTERY") (pin "NC2") (pinfunction "PAD2_NC2") (pintype "bidirectional"))
    )
    (net (code "62") (name "unconnected-(U3-NC-Pad11)") (class "Default")
      (node (ref "U3") (pin "11") (pinfunction "NC_11") (pintype "bidirectional"))
    )
    (net (code "63") (name "unconnected-(U3-NC-Pad15)") (class "Default")
      (node (ref "U3") (pin "15") (pinfunction "NC_15") (pintype "bidirectional"))
    )
  )
)
